# ARM_JTAG_Header_vertical.net
KiCad netlist of a schematic drawn in Altium Designer
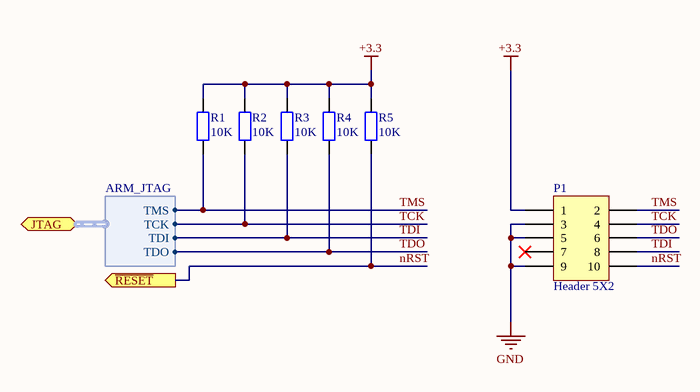
[diagram p0: ARM JTAG Header (vertical).SchDoc]

(export (version "E")
  (design (tool "Eeschema 10.0.6"))
  (components
    (comp (ref "P1")
      (value "Header 5X2")
      (footprint "FTSH-105-01-L-DV")
      (description "Header, 5-Pin, Dual row")
      (fields (field (name "PUBLISHER") "Altium Limited"))
      (libsource (lib "Miscellaneous Connectors") (part "Header 5X2"))
    )
    (comp (ref "R1")
      (value "10K")
      (footprint "R0603")
      (description "Resistor")
      (fields (field (name "Comment") "Res"))
      (libsource (lib "Miscellaneous Devices") (part "Res2"))
    )
    (comp (ref "R2")
      (value "10K")
      (footprint "R0603")
      (description "Resistor")
      (fields (field (name "Comment") "Res"))
      (libsource (lib "Miscellaneous Devices") (part "Res2"))
    )
    (comp (ref "R3")
      (value "10K")
      (footprint "R0603")
      (description "Resistor")
      (fields (field (name "Comment") "Res"))
      (libsource (lib "Miscellaneous Devices") (part "Res2"))
    )
    (comp (ref "R4")
      (value "10K")
      (footprint "R0603")
      (description "Resistor")
      (fields (field (name "Comment") "Res"))
      (libsource (lib "Miscellaneous Devices") (part "Res2"))
    )
    (comp (ref "R5")
      (value "10K")
      (footprint "R0603")
      (description "Resistor")
      (fields (field (name "Comment") "Res"))
      (libsource (lib "Miscellaneous Devices") (part "Res2"))
    )
  )
  (nets
    (net (code "2") (name "+3.3") (class "Default")
      (node (ref "P1") (pin "1") (pinfunction "1_1") (pintype "passive"))
      (node (ref "R1") (pin "2") (pinfunction "2_2") (pintype "passive"))
      (node (ref "R2") (pin "2") (pinfunction "2_2") (pintype "passive"))
      (node (ref "R3") (pin "2") (pinfunction "2_2") (pintype "passive"))
      (node (ref "R4") (pin "2") (pinfunction "2_2") (pintype "passive"))
      (node (ref "R5") (pin "2") (pinfunction "2_2") (pintype "passive"))
    )
    (net (code "3") (name "/TCK") (class "Default")
      (node (ref "P1") (pin "4") (pinfunction "4_4") (pintype "passive"))
      (node (ref "R2") (pin "1") (pinfunction "1_1") (pintype "passive"))
    )
    (net (code "4") (name "/TDI") (class "Default")
      (node (ref "P1") (pin "8") (pinfunction "8_8") (pintype "passive"))
      (node (ref "R3") (pin "1") (pinfunction "1_1") (pintype "passive"))
    )
    (net (code "5") (name "/TDO") (class "Default")
      (node (ref "P1") (pin "6") (pinfunction "6_6") (pintype "passive"))
      (node (ref "R4") (pin "1") (pinfunction "1_1") (pintype "passive"))
    )
    (net (code "6") (name "/TMS") (class "Default")
      (node (ref "P1") (pin "2") (pinfunction "2_2") (pintype "passive"))
      (node (ref "R1") (pin "1") (pinfunction "1_1") (pintype "passive"))
    )
    (net (code "7") (name "/nRST") (class "Default")
      (node (ref "P1") (pin "10") (pinfunction "10_10") (pintype "passive"))
      (node (ref "R5") (pin "1") (pinfunction "1_1") (pintype "passive"))
    )
    (net (code "9") (name "GND") (class "Default")
      (node (ref "P1") (pin "3") (pinfunction "3_3") (pintype "passive"))
      (node (ref "P1") (pin "5") (pinfunction "5_5") (pintype "passive"))
      (node (ref "P1") (pin "9") (pinfunction "9_9") (pintype "passive"))
    )
    (net (code "10") (name "unconnected-(P1-Pad7)") (class "Default")
      (node (ref "P1") (pin "7") (pinfunction "7_7") (pintype "passive+no_connect"))
    )
  )
)
